# NRV_BRK_OUT.net
KiCad netlist of a schematic drawn in Altium Designer
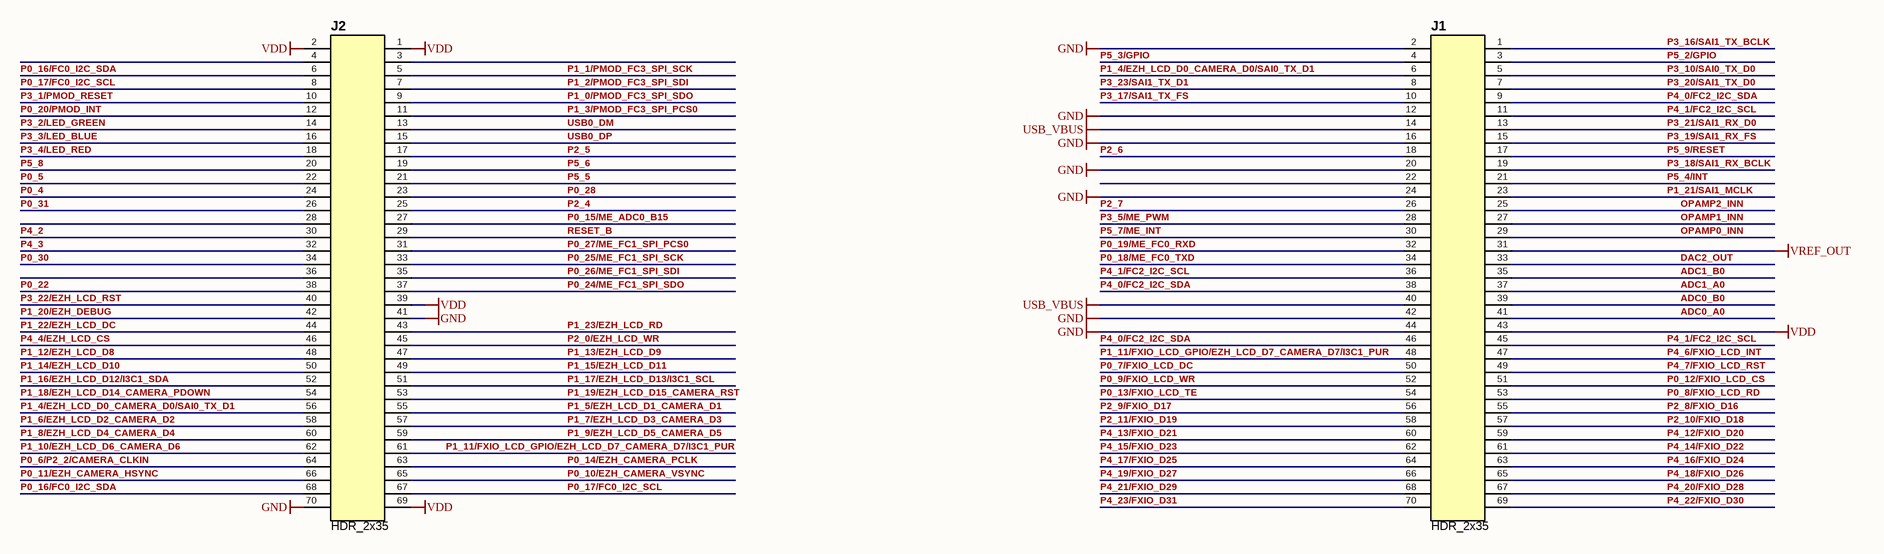
[diagram p0: NRV_BRK_OUT.SchDoc]

(export (version "E")
  (design (tool "Eeschema 10.0.6"))
  (components
    (comp (ref "J1")
      (value "HDR_2x35")
      (footprint "HEADER 2x35 .100\"")
      (description "2x35 Header .100\"")
      (libsource (lib "eConnector_Header") (part "HDR_2x35"))
    )
    (comp (ref "J2")
      (value "HDR_2x35")
      (footprint "HEADER 2x35 .100\"")
      (description "2x35 Header .100\"")
      (libsource (lib "eConnector_Header") (part "HDR_2x35"))
    )
  )
  (nets
    (net (code "1") (name "/ADC0_A0") (class "Default")
      (node (ref "J1") (pin "41") (pinfunction "41_41") (pintype "passive"))
    )
    (net (code "2") (name "/ADC0_B0") (class "Default")
      (node (ref "J1") (pin "39") (pinfunction "39_39") (pintype "passive"))
    )
    (net (code "3") (name "/ADC1_A0") (class "Default")
      (node (ref "J1") (pin "37") (pinfunction "37_37") (pintype "passive"))
    )
    (net (code "4") (name "/ADC1_B0") (class "Default")
      (node (ref "J1") (pin "35") (pinfunction "35_35") (pintype "passive"))
    )
    (net (code "5") (name "/DAC2_OUT") (class "Default")
      (node (ref "J1") (pin "33") (pinfunction "33_33") (pintype "passive"))
    )
    (net (code "6") (name "/OPAMP0_INN") (class "Default")
      (node (ref "J1") (pin "29") (pinfunction "29_29") (pintype "passive"))
    )
    (net (code "7") (name "/OPAMP1_INN") (class "Default")
      (node (ref "J1") (pin "27") (pinfunction "27_27") (pintype "passive"))
    )
    (net (code "8") (name "/OPAMP2_INN") (class "Default")
      (node (ref "J1") (pin "25") (pinfunction "25_25") (pintype "passive"))
    )
    (net (code "9") (name "/P0_4") (class "Default")
      (node (ref "J2") (pin "24") (pinfunction "24_24") (pintype "passive"))
    )
    (net (code "10") (name "/P0_5") (class "Default")
      (node (ref "J2") (pin "22") (pinfunction "22_22") (pintype "passive"))
    )
    (net (code "11") (name "/P0_6{slash}P2_2{slash}CAMERA_CLKIN") (class "Default")
      (node (ref "J2") (pin "64") (pinfunction "64_64") (pintype "passive"))
    )
    (net (code "12") (name "/P0_7{slash}FXIO_LCD_DC") (class "Default")
      (node (ref "J1") (pin "50") (pinfunction "50_50") (pintype "passive"))
    )
    (net (code "13") (name "/P0_8{slash}FXIO_LCD_RD") (class "Default")
      (node (ref "J1") (pin "53") (pinfunction "53_53") (pintype "passive"))
    )
    (net (code "14") (name "/P0_9{slash}FXIO_LCD_WR") (class "Default")
      (node (ref "J1") (pin "52") (pinfunction "52_52") (pintype "passive"))
    )
    (net (code "15") (name "/P0_10{slash}EZH_CAMERA_VSYNC") (class "Default")
      (node (ref "J2") (pin "65") (pinfunction "65_65") (pintype "passive"))
    )
    (net (code "16") (name "/P0_11{slash}EZH_CAMERA_HSYNC") (class "Default")
      (node (ref "J2") (pin "66") (pinfunction "66_66") (pintype "passive"))
    )
    (net (code "17") (name "/P0_12{slash}FXIO_LCD_CS") (class "Default")
      (node (ref "J1") (pin "51") (pinfunction "51_51") (pintype "passive"))
    )
    (net (code "18") (name "/P0_13{slash}FXIO_LCD_TE") (class "Default")
      (node (ref "J1") (pin "54") (pinfunction "54_54") (pintype "passive"))
    )
    (net (code "19") (name "/P0_14{slash}EZH_CAMERA_PCLK") (class "Default")
      (node (ref "J2") (pin "63") (pinfunction "63_63") (pintype "passive"))
    )
    (net (code "20") (name "/P0_15{slash}ME_ADC0_B15") (class "Default")
      (node (ref "J2") (pin "27") (pinfunction "27_27") (pintype "passive"))
    )
    (net (code "21") (name "/P0_16{slash}FC0_I2C_SDA") (class "Default")
      (node (ref "J2") (pin "6") (pinfunction "6_6") (pintype "passive"))
      (node (ref "J2") (pin "68") (pinfunction "68_68") (pintype "passive"))
    )
    (net (code "22") (name "/P0_17{slash}FC0_I2C_SCL") (class "Default")
      (node (ref "J2") (pin "67") (pinfunction "67_67") (pintype "passive"))
      (node (ref "J2") (pin "8") (pinfunction "8_8") (pintype "passive"))
    )
    (net (code "23") (name "/P0_18{slash}ME_FC0_TXD") (class "Default")
      (node (ref "J1") (pin "34") (pinfunction "34_34") (pintype "passive"))
    )
    (net (code "24") (name "/P0_19{slash}ME_FC0_RXD") (class "Default")
      (node (ref "J1") (pin "32") (pinfunction "32_32") (pintype "passive"))
    )
    (net (code "25") (name "/P0_20{slash}PMOD_INT") (class "Default")
      (node (ref "J2") (pin "12") (pinfunction "12_12") (pintype "passive"))
    )
    (net (code "26") (name "/P0_22") (class "Default")
      (node (ref "J2") (pin "38") (pinfunction "38_38") (pintype "passive"))
    )
    (net (code "27") (name "/P0_24{slash}ME_FC1_SPI_SDO") (class "Default")
      (node (ref "J2") (pin "37") (pinfunction "37_37") (pintype "passive"))
    )
    (net (code "28") (name "/P0_25{slash}ME_FC1_SPI_SCK") (class "Default")
      (node (ref "J2") (pin "33") (pinfunction "33_33") (pintype "passive"))
    )
    (net (code "29") (name "/P0_26{slash}ME_FC1_SPI_SDI") (class "Default")
      (node (ref "J2") (pin "35") (pinfunction "35_35") (pintype "passive"))
    )
    (net (code "30") (name "/P0_27{slash}ME_FC1_SPI_PCS0") (class "Default")
      (node (ref "J2") (pin "31") (pinfunction "31_31") (pintype "passive"))
    )
    (net (code "31") (name "/P0_28") (class "Default")
      (node (ref "J2") (pin "23") (pinfunction "23_23") (pintype "passive"))
    )
    (net (code "32") (name "/P0_30") (class "Default")
      (node (ref "J2") (pin "34") (pinfunction "34_34") (pintype "passive"))
    )
    (net (code "33") (name "/P0_31") (class "Default")
      (node (ref "J2") (pin "26") (pinfunction "26_26") (pintype "passive"))
    )
    (net (code "34") (name "/P1_0{slash}PMOD_FC3_SPI_SDO") (class "Default")
      (node (ref "J2") (pin "9") (pinfunction "9_9") (pintype "passive"))
    )
    (net (code "35") (name "/P1_1{slash}PMOD_FC3_SPI_SCK") (class "Default")
      (node (ref "J2") (pin "5") (pinfunction "5_5") (pintype "passive"))
    )
    (net (code "36") (name "/P1_2{slash}PMOD_FC3_SPI_SDI") (class "Default")
      (node (ref "J2") (pin "7") (pinfunction "7_7") (pintype "passive"))
    )
    (net (code "37") (name "/P1_3{slash}PMOD_FC3_SPI_PCS0") (class "Default")
      (node (ref "J2") (pin "11") (pinfunction "11_11") (pintype "passive"))
    )
    (net (code "38") (name "/P1_4{slash}EZH_LCD_D0_CAMERA_D0{slash}SAI0_TX_D1") (class "Default")
      (node (ref "J1") (pin "6") (pinfunction "6_6") (pintype "passive"))
      (node (ref "J2") (pin "56") (pinfunction "56_56") (pintype "passive"))
    )
    (net (code "39") (name "/P1_5{slash}EZH_LCD_D1_CAMERA_D1") (class "Default")
      (node (ref "J2") (pin "55") (pinfunction "55_55") (pintype "passive"))
    )
    (net (code "40") (name "/P1_6{slash}EZH_LCD_D2_CAMERA_D2") (class "Default")
      (node (ref "J2") (pin "58") (pinfunction "58_58") (pintype "passive"))
    )
    (net (code "41") (name "/P1_7{slash}EZH_LCD_D3_CAMERA_D3") (class "Default")
      (node (ref "J2") (pin "57") (pinfunction "57_57") (pintype "passive"))
    )
    (net (code "42") (name "/P1_8{slash}EZH_LCD_D4_CAMERA_D4") (class "Default")
      (node (ref "J2") (pin "60") (pinfunction "60_60") (pintype "passive"))
    )
    (net (code "43") (name "/P1_9{slash}EZH_LCD_D5_CAMERA_D5") (class "Default")
      (node (ref "J2") (pin "59") (pinfunction "59_59") (pintype "passive"))
    )
    (net (code "44") (name "/P1_10{slash}EZH_LCD_D6_CAMERA_D6") (class "Default")
      (node (ref "J2") (pin "62") (pinfunction "62_62") (pintype "passive"))
    )
    (net (code "45") (name "/P1_11{slash}FXIO_LCD_GPIO{slash}EZH_LCD_D7_CAMERA_D7{slash}I3C1_PUR") (class "Default")
      (node (ref "J1") (pin "48") (pinfunction "48_48") (pintype "passive"))
      (node (ref "J2") (pin "61") (pinfunction "61_61") (pintype "passive"))
    )
    (net (code "46") (name "/P1_12{slash}EZH_LCD_D8") (class "Default")
      (node (ref "J2") (pin "48") (pinfunction "48_48") (pintype "passive"))
    )
    (net (code "47") (name "/P1_13{slash}EZH_LCD_D9") (class "Default")
      (node (ref "J2") (pin "47") (pinfunction "47_47") (pintype "passive"))
    )
    (net (code "48") (name "/P1_14{slash}EZH_LCD_D10") (class "Default")
      (node (ref "J2") (pin "50") (pinfunction "50_50") (pintype "passive"))
    )
    (net (code "49") (name "/P1_15{slash}EZH_LCD_D11") (class "Default")
      (node (ref "J2") (pin "49") (pinfunction "49_49") (pintype "passive"))
    )
    (net (code "50") (name "/P1_16{slash}EZH_LCD_D12{slash}I3C1_SDA") (class "Default")
      (node (ref "J2") (pin "52") (pinfunction "52_52") (pintype "passive"))
    )
    (net (code "51") (name "/P1_17{slash}EZH_LCD_D13{slash}I3C1_SCL") (class "Default")
      (node (ref "J2") (pin "51") (pinfunction "51_51") (pintype "passive"))
    )
    (net (code "52") (name "/P1_18{slash}EZH_LCD_D14_CAMERA_PDOWN") (class "Default")
      (node (ref "J2") (pin "54") (pinfunction "54_54") (pintype "passive"))
    )
    (net (code "53") (name "/P1_19{slash}EZH_LCD_D15_CAMERA_RST") (class "Default")
      (node (ref "J2") (pin "53") (pinfunction "53_53") (pintype "passive"))
    )
    (net (code "54") (name "/P1_20{slash}EZH_DEBUG") (class "Default")
      (node (ref "J2") (pin "42") (pinfunction "42_42") (pintype "passive"))
    )
    (net (code "55") (name "/P1_21{slash}SAI1_MCLK") (class "Default")
      (node (ref "J1") (pin "23") (pinfunction "23_23") (pintype "passive"))
    )
    (net (code "56") (name "/P1_22{slash}EZH_LCD_DC") (class "Default")
      (node (ref "J2") (pin "44") (pinfunction "44_44") (pintype "passive"))
    )
    (net (code "57") (name "/P1_23{slash}EZH_LCD_RD") (class "Default")
      (node (ref "J2") (pin "43") (pinfunction "43_43") (pintype "passive"))
    )
    (net (code "58") (name "/P2_0{slash}EZH_LCD_WR") (class "Default")
      (node (ref "J2") (pin "45") (pinfunction "45_45") (pintype "passive"))
    )
    (net (code "59") (name "/P2_4") (class "Default")
      (node (ref "J2") (pin "25") (pinfunction "25_25") (pintype "passive"))
    )
    (net (code "60") (name "/P2_5") (class "Default")
      (node (ref "J2") (pin "17") (pinfunction "17_17") (pintype "passive"))
    )
    (net (code "61") (name "/P2_6") (class "Default")
      (node (ref "J1") (pin "18") (pinfunction "18_18") (pintype "passive"))
    )
    (net (code "62") (name "/P2_7") (class "Default")
      (node (ref "J1") (pin "26") (pinfunction "26_26") (pintype "passive"))
    )
    (net (code "63") (name "/P2_8{slash}FXIO_D16") (class "Default")
      (node (ref "J1") (pin "55") (pinfunction "55_55") (pintype "passive"))
    )
    (net (code "64") (name "/P2_9{slash}FXIO_D17") (class "Default")
      (node (ref "J1") (pin "56") (pinfunction "56_56") (pintype "passive"))
    )
    (net (code "65") (name "/P2_10{slash}FXIO_D18") (class "Default")
      (node (ref "J1") (pin "57") (pinfunction "57_57") (pintype "passive"))
    )
    (net (code "66") (name "/P2_11{slash}FXIO_D19") (class "Default")
      (node (ref "J1") (pin "58") (pinfunction "58_58") (pintype "passive"))
    )
    (net (code "67") (name "/P3_1{slash}PMOD_RESET") (class "Default")
      (node (ref "J2") (pin "10") (pinfunction "10_10") (pintype "passive"))
    )
    (net (code "68") (name "/P3_2{slash}LED_GREEN") (class "Default")
      (node (ref "J2") (pin "14") (pinfunction "14_14") (pintype "passive"))
    )
    (net (code "69") (name "/P3_3{slash}LED_BLUE") (class "Default")
      (node (ref "J2") (pin "16") (pinfunction "16_16") (pintype "passive"))
    )
    (net (code "70") (name "/P3_4{slash}LED_RED") (class "Default")
      (node (ref "J2") (pin "18") (pinfunction "18_18") (pintype "passive"))
    )
    (net (code "71") (name "/P3_5{slash}ME_PWM") (class "Default")
      (node (ref "J1") (pin "28") (pinfunction "28_28") (pintype "passive"))
    )
    (net (code "72") (name "/P3_10{slash}SAI0_TX_D0") (class "Default")
      (node (ref "J1") (pin "5") (pinfunction "5_5") (pintype "passive"))
    )
    (net (code "73") (name "/P3_16{slash}SAI1_TX_BCLK") (class "Default")
      (node (ref "J1") (pin "1") (pinfunction "1_1") (pintype "passive"))
    )
    (net (code "74") (name "/P3_17{slash}SAI1_TX_FS") (class "Default")
      (node (ref "J1") (pin "10") (pinfunction "10_10") (pintype "passive"))
    )
    (net (code "75") (name "/P3_18{slash}SAI1_RX_BCLK") (class "Default")
      (node (ref "J1") (pin "19") (pinfunction "19_19") (pintype "passive"))
    )
    (net (code "76") (name "/P3_19{slash}SAI1_RX_FS") (class "Default")
      (node (ref "J1") (pin "15") (pinfunction "15_15") (pintype "passive"))
    )
    (net (code "77") (name "/P3_20{slash}SAI1_TX_D0") (class "Default")
      (node (ref "J1") (pin "7") (pinfunction "7_7") (pintype "passive"))
    )
    (net (code "78") (name "/P3_21{slash}SAI1_RX_D0") (class "Default")
      (node (ref "J1") (pin "13") (pinfunction "13_13") (pintype "passive"))
    )
    (net (code "79") (name "/P3_22{slash}EZH_LCD_RST") (class "Default")
      (node (ref "J2") (pin "40") (pinfunction "40_40") (pintype "passive"))
    )
    (net (code "80") (name "/P3_23{slash}SAI1_TX_D1") (class "Default")
      (node (ref "J1") (pin "8") (pinfunction "8_8") (pintype "passive"))
    )
    (net (code "81") (name "/P4_0{slash}FC2_I2C_SDA") (class "Default")
      (node (ref "J1") (pin "38") (pinfunction "38_38") (pintype "passive"))
      (node (ref "J1") (pin "46") (pinfunction "46_46") (pintype "passive"))
      (node (ref "J1") (pin "9") (pinfunction "9_9") (pintype "passive"))
    )
    (net (code "82") (name "/P4_1{slash}FC2_I2C_SCL") (class "Default")
      (node (ref "J1") (pin "11") (pinfunction "11_11") (pintype "passive"))
      (node (ref "J1") (pin "36") (pinfunction "36_36") (pintype "passive"))
      (node (ref "J1") (pin "45") (pinfunction "45_45") (pintype "passive"))
    )
    (net (code "83") (name "/P4_2") (class "Default")
      (node (ref "J2") (pin "30") (pinfunction "30_30") (pintype "passive"))
    )
    (net (code "84") (name "/P4_3") (class "Default")
      (node (ref "J2") (pin "32") (pinfunction "32_32") (pintype "passive"))
    )
    (net (code "85") (name "/P4_4{slash}EZH_LCD_CS") (class "Default")
      (node (ref "J2") (pin "46") (pinfunction "46_46") (pintype "passive"))
    )
    (net (code "86") (name "/P4_6{slash}FXIO_LCD_INT") (class "Default")
      (node (ref "J1") (pin "47") (pinfunction "47_47") (pintype "passive"))
    )
    (net (code "87") (name "/P4_7{slash}FXIO_LCD_RST") (class "Default")
      (node (ref "J1") (pin "49") (pinfunction "49_49") (pintype "passive"))
    )
    (net (code "88") (name "/P4_12{slash}FXIO_D20") (class "Default")
      (node (ref "J1") (pin "59") (pinfunction "59_59") (pintype "passive"))
    )
    (net (code "89") (name "/P4_13{slash}FXIO_D21") (class "Default")
      (node (ref "J1") (pin "60") (pinfunction "60_60") (pintype "passive"))
    )
    (net (code "90") (name "/P4_14{slash}FXIO_D22") (class "Default")
      (node (ref "J1") (pin "61") (pinfunction "61_61") (pintype "passive"))
    )
    (net (code "91") (name "/P4_15{slash}FXIO_D23") (class "Default")
      (node (ref "J1") (pin "62") (pinfunction "62_62") (pintype "passive"))
    )
    (net (code "92") (name "/P4_16{slash}FXIO_D24") (class "Default")
      (node (ref "J1") (pin "63") (pinfunction "63_63") (pintype "passive"))
    )
    (net (code "93") (name "/P4_17{slash}FXIO_D25") (class "Default")
      (node (ref "J1") (pin "64") (pinfunction "64_64") (pintype "passive"))
    )
    (net (code "94") (name "/P4_18{slash}FXIO_D26") (class "Default")
      (node (ref "J1") (pin "65") (pinfunction "65_65") (pintype "passive"))
    )
    (net (code "95") (name "/P4_19{slash}FXIO_D27") (class "Default")
      (node (ref "J1") (pin "66") (pinfunction "66_66") (pintype "passive"))
    )
    (net (code "96") (name "/P4_20{slash}FXIO_D28") (class "Default")
      (node (ref "J1") (pin "67") (pinfunction "67_67") (pintype "passive"))
    )
    (net (code "97") (name "/P4_21{slash}FXIO_D29") (class "Default")
      (node (ref "J1") (pin "68") (pinfunction "68_68") (pintype "passive"))
    )
    (net (code "98") (name "/P4_22{slash}FXIO_D30") (class "Default")
      (node (ref "J1") (pin "69") (pinfunction "69_69") (pintype "passive"))
    )
    (net (code "99") (name "/P4_23{slash}FXIO_D31") (class "Default")
      (node (ref "J1") (pin "70") (pinfunction "70_70") (pintype "passive"))
    )
    (net (code "100") (name "/P5_2{slash}GPIO") (class "Default")
      (node (ref "J1") (pin "3") (pinfunction "3_3") (pintype "passive"))
    )
    (net (code "101") (name "/P5_3{slash}GPIO") (class "Default")
      (node (ref "J1") (pin "4") (pinfunction "4_4") (pintype "passive"))
    )
    (net (code "102") (name "/P5_4{slash}INT") (class "Default")
      (node (ref "J1") (pin "21") (pinfunction "21_21") (pintype "passive"))
    )
    (net (code "103") (name "/P5_5") (class "Default")
      (node (ref "J2") (pin "21") (pinfunction "21_21") (pintype "passive"))
    )
    (net (code "104") (name "/P5_6") (class "Default")
      (node (ref "J2") (pin "19") (pinfunction "19_19") (pintype "passive"))
    )
    (net (code "105") (name "/P5_7{slash}ME_INT") (class "Default")
      (node (ref "J1") (pin "30") (pinfunction "30_30") (pintype "passive"))
    )
    (net (code "106") (name "/P5_8") (class "Default")
      (node (ref "J2") (pin "20") (pinfunction "20_20") (pintype "passive"))
    )
    (net (code "107") (name "/P5_9{slash}RESET") (class "Default")
      (node (ref "J1") (pin "17") (pinfunction "17_17") (pintype "passive"))
    )
    (net (code "108") (name "/RESET_B") (class "Default")
      (node (ref "J2") (pin "29") (pinfunction "29_29") (pintype "passive"))
    )
    (net (code "109") (name "/USB0_DM") (class "Default")
      (node (ref "J2") (pin "13") (pinfunction "13_13") (pintype "passive"))
    )
    (net (code "110") (name "/USB0_DP") (class "Default")
      (node (ref "J2") (pin "15") (pinfunction "15_15") (pintype "passive"))
    )
    (net (code "111") (name "GND") (class "Default")
      (node (ref "J1") (pin "12") (pinfunction "12_12") (pintype "passive"))
      (node (ref "J1") (pin "16") (pinfunction "16_16") (pintype "passive"))
      (node (ref "J1") (pin "2") (pinfunction "2_2") (pintype "passive"))
      (node (ref "J1") (pin "20") (pinfunction "20_20") (pintype "passive"))
      (node (ref "J1") (pin "24") (pinfunction "24_24") (pintype "passive"))
      (node (ref "J1") (pin "42") (pinfunction "42_42") (pintype "passive"))
      (node (ref "J1") (pin "44") (pinfunction "44_44") (pintype "passive"))
      (node (ref "J2") (pin "41") (pinfunction "41_41") (pintype "passive"))
      (node (ref "J2") (pin "70") (pinfunction "70_70") (pintype "passive"))
    )
    (net (code "112") (name "USB_VBUS") (class "Default")
      (node (ref "J1") (pin "14") (pinfunction "14_14") (pintype "passive"))
      (node (ref "J1") (pin "40") (pinfunction "40_40") (pintype "passive"))
    )
    (net (code "113") (name "VDD") (class "Default")
      (node (ref "J1") (pin "43") (pinfunction "43_43") (pintype "passive"))
      (node (ref "J2") (pin "1") (pinfunction "1_1") (pintype "passive"))
      (node (ref "J2") (pin "2") (pinfunction "2_2") (pintype "passive"))
      (node (ref "J2") (pin "39") (pinfunction "39_39") (pintype "passive"))
      (node (ref "J2") (pin "69") (pinfunction "69_69") (pintype "passive"))
    )
    (net (code "114") (name "VREF_OUT") (class "Default")
      (node (ref "J1") (pin "31") (pinfunction "31_31") (pintype "passive"))
    )
    (net (code "115") (name "unconnected-(J1-Pad22)") (class "Default")
      (node (ref "J1") (pin "22") (pinfunction "22_22") (pintype "passive"))
    )
    (net (code "116") (name "unconnected-(J2-Pad3)") (class "Default")
      (node (ref "J2") (pin "3") (pinfunction "3_3") (pintype "passive"))
    )
    (net (code "117") (name "unconnected-(J2-Pad4)") (class "Default")
      (node (ref "J2") (pin "4") (pinfunction "4_4") (pintype "passive"))
    )
    (net (code "118") (name "unconnected-(J2-Pad28)") (class "Default")
      (node (ref "J2") (pin "28") (pinfunction "28_28") (pintype "passive"))
    )
    (net (code "119") (name "unconnected-(J2-Pad36)") (class "Default")
      (node (ref "J2") (pin "36") (pinfunction "36_36") (pintype "passive"))
    )
  )
)
